# atmega.net
KiCad netlist of a schematic drawn in EAGLE
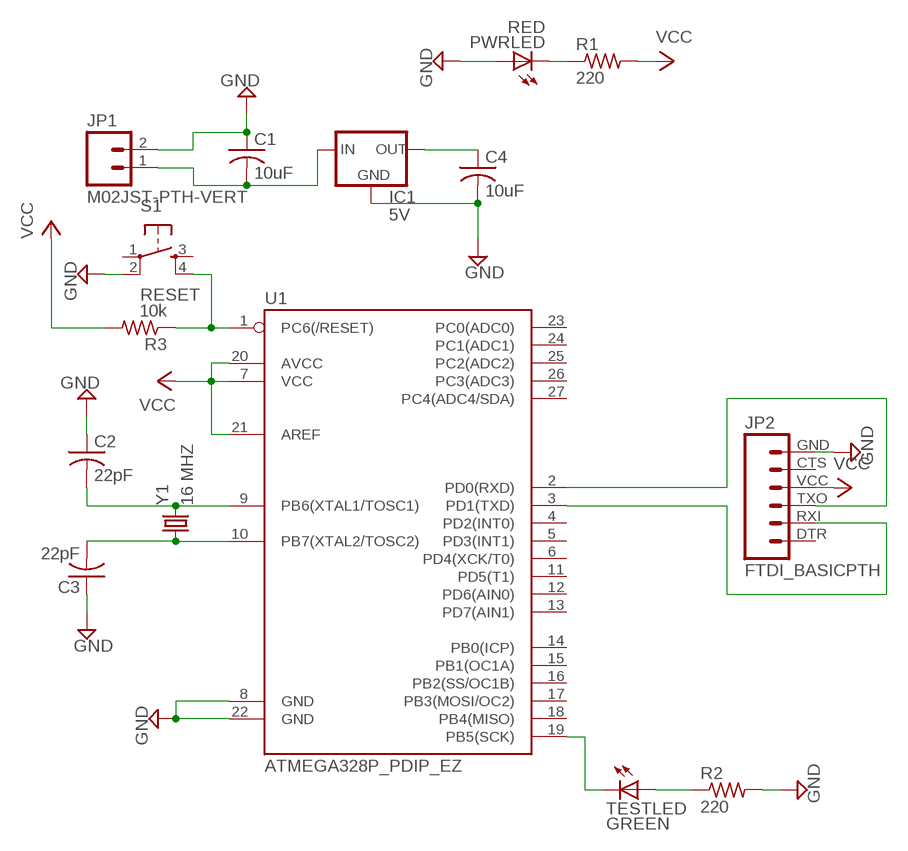
[diagram p0: schematic, sheet 1]

(export (version "E")
  (design (tool "Eeschema 10.0.6"))
  (components
    (comp (ref "C1")
      (value "10uF")
      (footprint "eagle-import:C0805")
      (libsource (lib "eagle-import") (part "C-USC0805"))
    )
    (comp (ref "C2")
      (value "22pF")
      (footprint "eagle-import:C0805")
      (libsource (lib "eagle-import") (part "C-USC0805"))
    )
    (comp (ref "C3")
      (value "22pF")
      (footprint "eagle-import:C0805")
      (libsource (lib "eagle-import") (part "C-USC0805"))
    )
    (comp (ref "C4")
      (value "10uF")
      (footprint "eagle-import:C0805")
      (libsource (lib "eagle-import") (part "C-USC0805"))
    )
    (comp (ref "IC1")
      (value "5V")
      (footprint "eagle-import:TO220-IGO")
      (libsource (lib "eagle-import") (part "V_REG_78XXSINK"))
    )
    (comp (ref "JP1")
      (value "M02JST-PTH-VERT")
      (footprint "eagle-import:JST-2-PTH-VERT")
      (libsource (lib "eagle-import") (part "M02JST-PTH-VERT"))
    )
    (comp (ref "JP2")
      (value "FTDI_BASICPTH")
      (footprint "eagle-import:FTDI_BASIC")
      (libsource (lib "eagle-import") (part "FTDI_BASICPTH"))
    )
    (comp (ref "PWRLED")
      (value "RED")
      (footprint "eagle-import:CHIPLED_0805")
      (libsource (lib "eagle-import") (part "LEDCHIPLED_0805"))
    )
    (comp (ref "R1")
      (value "220")
      (footprint "eagle-import:R0805")
      (libsource (lib "eagle-import") (part "R-US_R0805"))
    )
    (comp (ref "R2")
      (value "220")
      (footprint "eagle-import:R0805")
      (libsource (lib "eagle-import") (part "R-US_R0805"))
    )
    (comp (ref "R3")
      (value "10k")
      (footprint "eagle-import:R0805")
      (libsource (lib "eagle-import") (part "R-US_R0805"))
    )
    (comp (ref "S1")
      (value "RESET")
      (footprint "eagle-import:TACTILE_SWITCH_SMD")
      (libsource (lib "eagle-import") (part "TAC_SWITCHSMD"))
    )
    (comp (ref "TESTLED")
      (value "GREEN")
      (footprint "eagle-import:CHIPLED_0805")
      (libsource (lib "eagle-import") (part "LEDCHIPLED_0805"))
    )
    (comp (ref "U1")
      (value "ATMEGA328P_PDIP_EZ")
      (footprint "eagle-import:DIL28-EZ")
      (libsource (lib "eagle-import") (part "ATMEGA328P_PDIP_EZ"))
    )
    (comp (ref "Y1")
      (value "16 MHZ")
      (footprint "eagle-import:HC49US")
      (libsource (lib "eagle-import") (part "CRYSTALHC49US"))
    )
  )
  (nets
    (net (code "1") (name "GND") (class "Default")
      (node (ref "C1") (pin "1") (pinfunction "1_1") (pintype "passive"))
      (node (ref "C2") (pin "1") (pinfunction "1_1") (pintype "passive"))
      (node (ref "C3") (pin "1") (pinfunction "1_1") (pintype "passive"))
      (node (ref "C4") (pin "2") (pinfunction "2_2") (pintype "passive"))
      (node (ref "IC1") (pin "GND") (pinfunction "GND_GND") (pintype "input"))
      (node (ref "JP1") (pin "2") (pinfunction "2_2") (pintype "passive"))
      (node (ref "JP2") (pin "GND") (pinfunction "6_GND") (pintype "passive"))
      (node (ref "PWRLED") (pin "A") (pinfunction "A_A") (pintype "passive"))
      (node (ref "R2") (pin "2") (pinfunction "2_2") (pintype "passive"))
      (node (ref "S1") (pin "2") (pinfunction "2_2") (pintype "passive"))
      (node (ref "U1") (pin "22") (pinfunction "GND_22") (pintype "bidirectional"))
      (node (ref "U1") (pin "8") (pinfunction "GND_8") (pintype "bidirectional"))
    )
    (net (code "2") (name "Net-(C1-Pad2)") (class "Default")
      (node (ref "C1") (pin "2") (pinfunction "2_2") (pintype "passive"))
      (node (ref "IC1") (pin "IN") (pinfunction "IN_IN") (pintype "input"))
      (node (ref "JP1") (pin "1") (pinfunction "1_1") (pintype "passive"))
    )
    (net (code "3") (name "Net-(C4-Pad1)") (class "Default")
      (node (ref "C4") (pin "1") (pinfunction "1_1") (pintype "passive"))
      (node (ref "IC1") (pin "OUT") (pinfunction "OUT_OUT") (pintype "output"))
    )
    (net (code "4") (name "Net-(JP2-2)") (class "Default")
      (node (ref "JP2") (pin "RXI") (pinfunction "2_RXI") (pintype "passive"))
      (node (ref "U1") (pin "3") (pinfunction "PD1(TXD)_3") (pintype "bidirectional"))
    )
    (net (code "5") (name "Net-(JP2-3)") (class "Default")
      (node (ref "JP2") (pin "TXO") (pinfunction "3_TXO") (pintype "passive"))
      (node (ref "U1") (pin "2") (pinfunction "PD0(RXD)_2") (pintype "bidirectional"))
    )
    (net (code "6") (name "Net-(PWRLED-PadC)") (class "Default")
      (node (ref "PWRLED") (pin "C") (pinfunction "C_C") (pintype "passive"))
      (node (ref "R1") (pin "1") (pinfunction "1_1") (pintype "passive"))
    )
    (net (code "7") (name "Net-(R2-Pad1)") (class "Default")
      (node (ref "R2") (pin "1") (pinfunction "1_1") (pintype "passive"))
      (node (ref "TESTLED") (pin "A") (pinfunction "A_A") (pintype "passive"))
    )
    (net (code "8") (name "Net-(U1-PB5(SCK))") (class "Default")
      (node (ref "TESTLED") (pin "C") (pinfunction "C_C") (pintype "passive"))
      (node (ref "U1") (pin "19") (pinfunction "PB5(SCK)_19") (pintype "bidirectional"))
    )
    (net (code "9") (name "Net-(U1-PB6(XTAL1{slash}TOSC1))") (class "Default")
      (node (ref "C2") (pin "2") (pinfunction "2_2") (pintype "passive"))
      (node (ref "U1") (pin "9") (pinfunction "PB6(XTAL1/TOSC1)_9") (pintype "bidirectional"))
      (node (ref "Y1") (pin "2") (pinfunction "2_2") (pintype "passive"))
    )
    (net (code "10") (name "Net-(U1-PB7(XTAL2{slash}TOSC2))") (class "Default")
      (node (ref "C3") (pin "2") (pinfunction "2_2") (pintype "passive"))
      (node (ref "U1") (pin "10") (pinfunction "PB7(XTAL2/TOSC2)_10") (pintype "bidirectional"))
      (node (ref "Y1") (pin "1") (pinfunction "1_1") (pintype "passive"))
    )
    (net (code "11") (name "Net-(U1-PC6({slash}RESET))") (class "Default")
      (node (ref "R3") (pin "1") (pinfunction "1_1") (pintype "passive"))
      (node (ref "S1") (pin "4") (pinfunction "4_4") (pintype "passive"))
      (node (ref "U1") (pin "1") (pinfunction "PC6(/RESET)_1") (pintype "bidirectional"))
    )
    (net (code "12") (name "VCC") (class "Default")
      (node (ref "JP2") (pin "VCC") (pinfunction "4_VCC") (pintype "passive"))
      (node (ref "R1") (pin "2") (pinfunction "2_2") (pintype "passive"))
      (node (ref "R3") (pin "2") (pinfunction "2_2") (pintype "passive"))
      (node (ref "U1") (pin "20") (pinfunction "AVCC_20") (pintype "bidirectional"))
      (node (ref "U1") (pin "21") (pinfunction "AREF_21") (pintype "bidirectional"))
      (node (ref "U1") (pin "7") (pinfunction "VCC_7") (pintype "bidirectional"))
    )
    (net (code "13") (name "unconnected-(JP2-1-PadDTR)") (class "Default")
      (node (ref "JP2") (pin "DTR") (pinfunction "1_DTR") (pintype "passive"))
    )
    (net (code "14") (name "unconnected-(JP2-5-PadCTS)") (class "Default")
      (node (ref "JP2") (pin "CTS") (pinfunction "5_CTS") (pintype "passive"))
    )
    (net (code "15") (name "unconnected-(S1-Pad1)") (class "Default")
      (node (ref "S1") (pin "1") (pinfunction "1_1") (pintype "passive"))
    )
    (net (code "16") (name "unconnected-(S1-Pad3)") (class "Default")
      (node (ref "S1") (pin "3") (pinfunction "3_3") (pintype "passive"))
    )
    (net (code "17") (name "unconnected-(U1-PB0(ICP)-Pad14)") (class "Default")
      (node (ref "U1") (pin "14") (pinfunction "PB0(ICP)_14") (pintype "bidirectional"))
    )
    (net (code "18") (name "unconnected-(U1-PB1(OC1A)-Pad15)") (class "Default")
      (node (ref "U1") (pin "15") (pinfunction "PB1(OC1A)_15") (pintype "bidirectional"))
    )
    (net (code "19") (name "unconnected-(U1-PB2(SS{slash}OC1B)-Pad16)") (class "Default")
      (node (ref "U1") (pin "16") (pinfunction "PB2(SS/OC1B)_16") (pintype "bidirectional"))
    )
    (net (code "20") (name "unconnected-(U1-PB3(MOSI{slash}OC2)-Pad17)") (class "Default")
      (node (ref "U1") (pin "17") (pinfunction "PB3(MOSI/OC2)_17") (pintype "bidirectional"))
    )
    (net (code "21") (name "unconnected-(U1-PB4(MISO)-Pad18)") (class "Default")
      (node (ref "U1") (pin "18") (pinfunction "PB4(MISO)_18") (pintype "bidirectional"))
    )
    (net (code "22") (name "unconnected-(U1-PC0(ADC0)-Pad23)") (class "Default")
      (node (ref "U1") (pin "23") (pinfunction "PC0(ADC0)_23") (pintype "bidirectional"))
    )
    (net (code "23") (name "unconnected-(U1-PC1(ADC1)-Pad24)") (class "Default")
      (node (ref "U1") (pin "24") (pinfunction "PC1(ADC1)_24") (pintype "bidirectional"))
    )
    (net (code "24") (name "unconnected-(U1-PC2(ADC2)-Pad25)") (class "Default")
      (node (ref "U1") (pin "25") (pinfunction "PC2(ADC2)_25") (pintype "bidirectional"))
    )
    (net (code "25") (name "unconnected-(U1-PC3(ADC3)-Pad26)") (class "Default")
      (node (ref "U1") (pin "26") (pinfunction "PC3(ADC3)_26") (pintype "bidirectional"))
    )
    (net (code "26") (name "unconnected-(U1-PC4(ADC4{slash}SDA)-Pad27)") (class "Default")
      (node (ref "U1") (pin "27") (pinfunction "PC4(ADC4/SDA)_27") (pintype "bidirectional"))
    )
    (net (code "27") (name "unconnected-(U1-PD2(INT0)-Pad4)") (class "Default")
      (node (ref "U1") (pin "4") (pinfunction "PD2(INT0)_4") (pintype "bidirectional"))
    )
    (net (code "28") (name "unconnected-(U1-PD3(INT1)-Pad5)") (class "Default")
      (node (ref "U1") (pin "5") (pinfunction "PD3(INT1)_5") (pintype "bidirectional"))
    )
    (net (code "29") (name "unconnected-(U1-PD4(XCK{slash}T0)-Pad6)") (class "Default")
      (node (ref "U1") (pin "6") (pinfunction "PD4(XCK/T0)_6") (pintype "bidirectional"))
    )
    (net (code "30") (name "unconnected-(U1-PD5(T1)-Pad11)") (class "Default")
      (node (ref "U1") (pin "11") (pinfunction "PD5(T1)_11") (pintype "bidirectional"))
    )
    (net (code "31") (name "unconnected-(U1-PD6(AIN0)-Pad12)") (class "Default")
      (node (ref "U1") (pin "12") (pinfunction "PD6(AIN0)_12") (pintype "bidirectional"))
    )
    (net (code "32") (name "unconnected-(U1-PD7(AIN1)-Pad13)") (class "Default")
      (node (ref "U1") (pin "13") (pinfunction "PD7(AIN1)_13") (pintype "bidirectional"))
    )
  )
)
